# Input_switch.net
KiCad netlist of a schematic drawn in Altium Designer
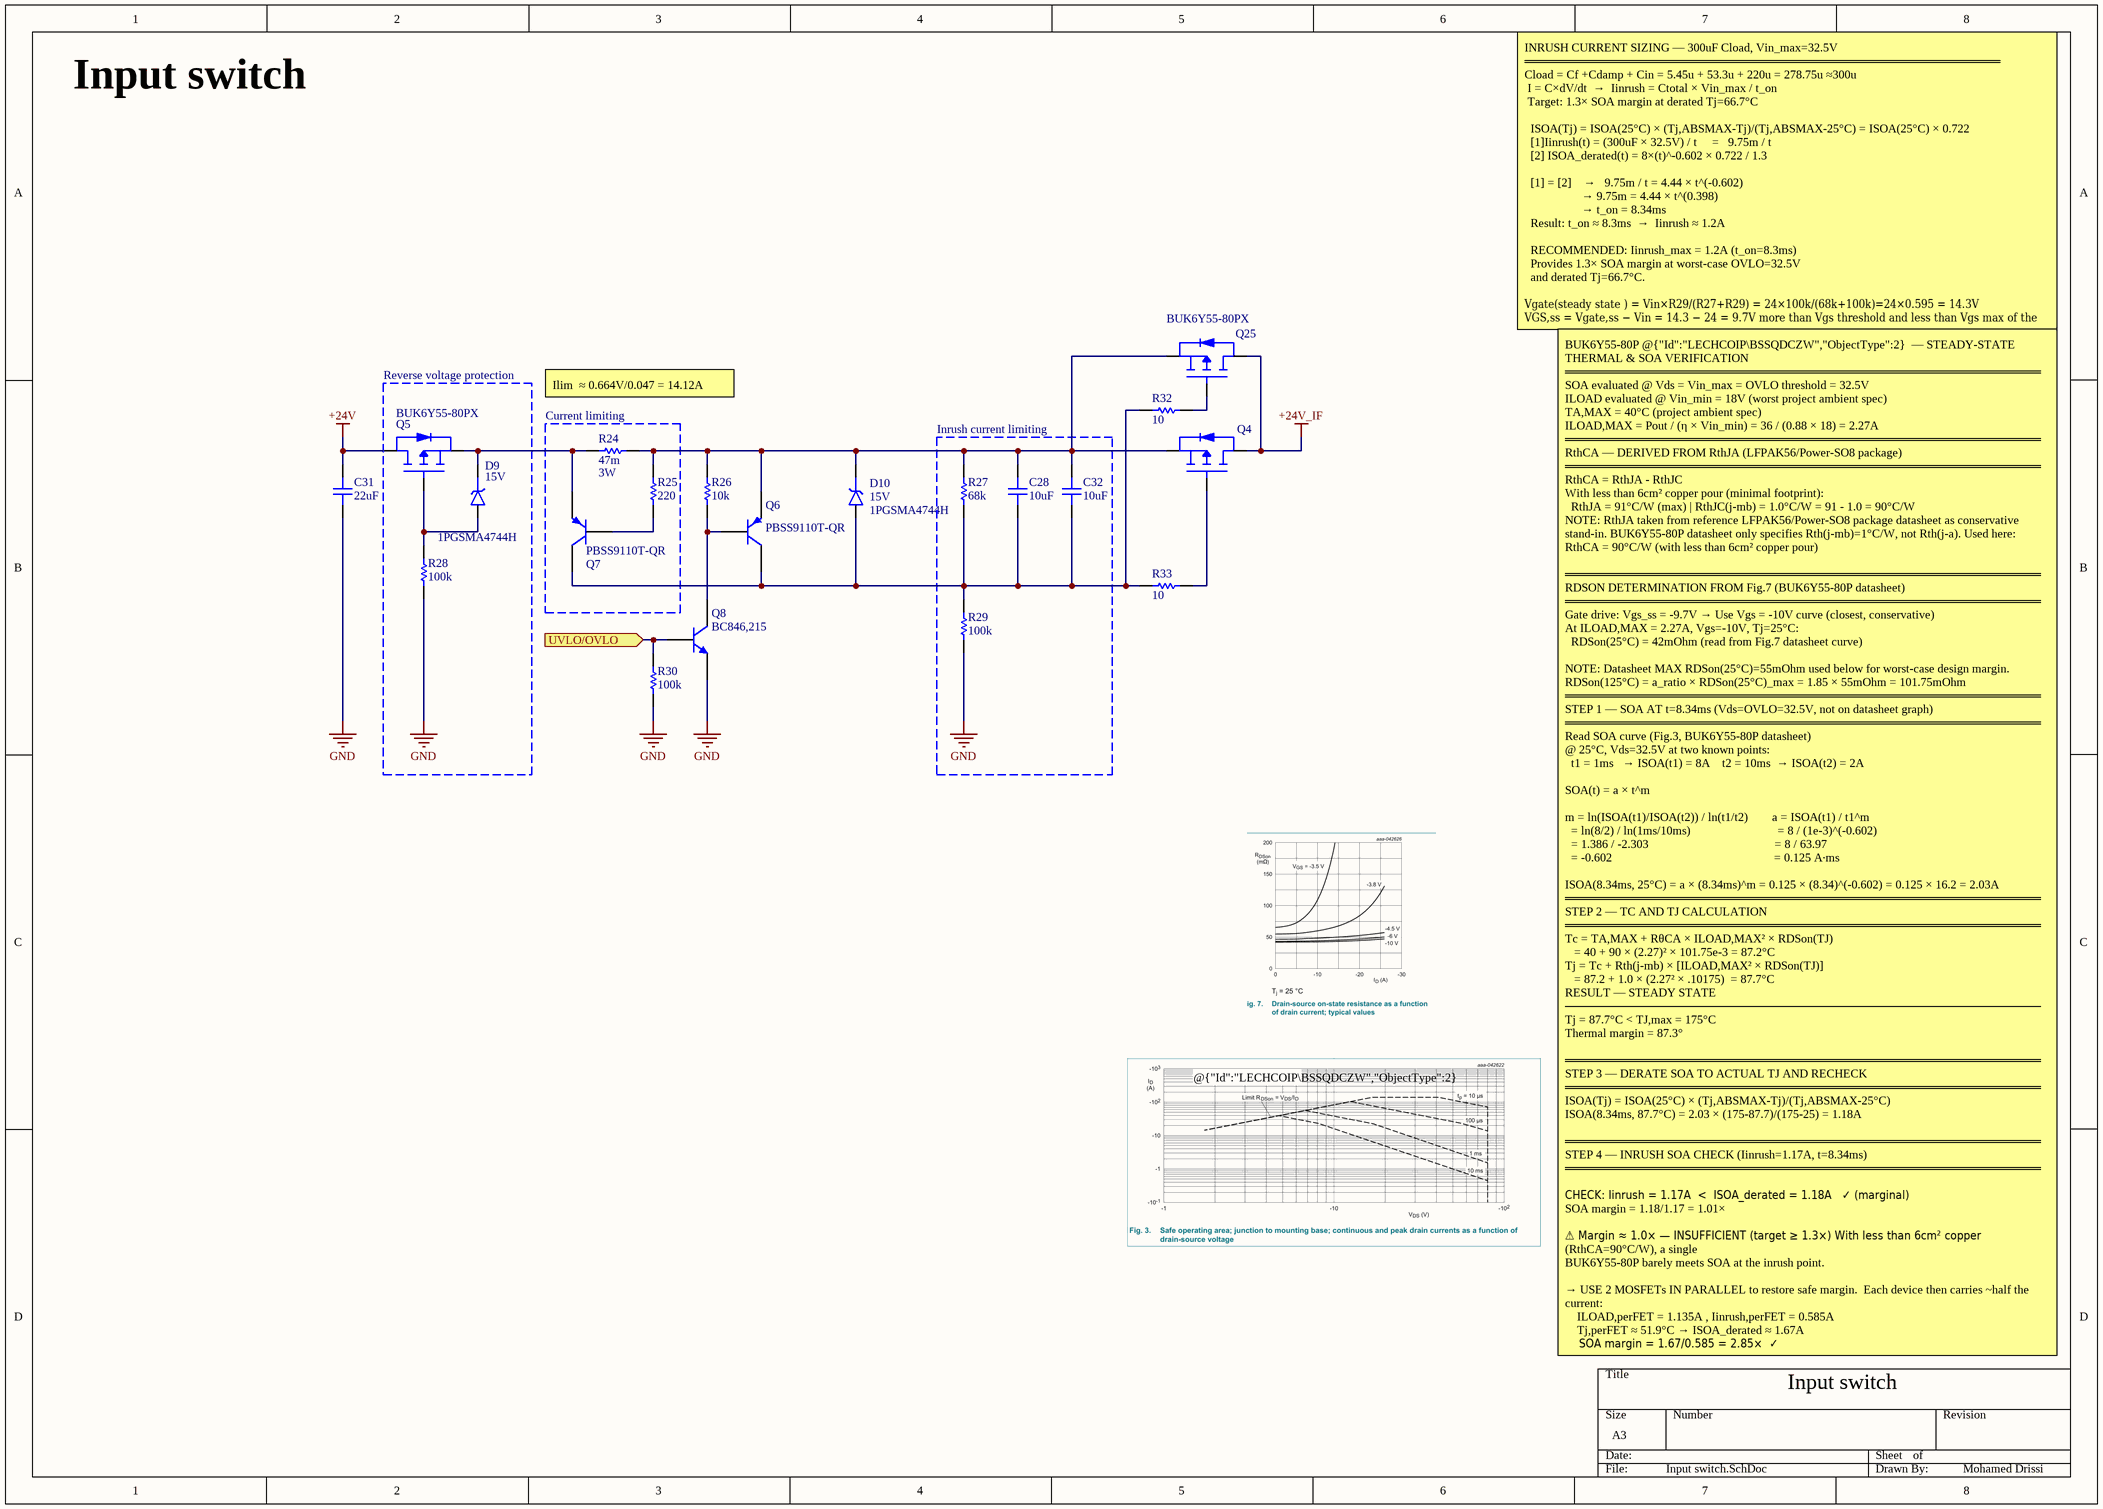
[diagram p0: Input switch.SchDoc]

(export (version "E")
  (design (tool "Eeschema 10.0.6"))
  (components
    (comp (ref "C28")
      (value "GRM32EC72A106KE05L")
      (footprint "cap_1210")
      (description "100V 10uF X7S ±10% 1210 Multilayer Ceramic Capacitors MLCC - SMD/SMT ROHS")
      (fields
        (field (name "MANUFACTURER") "Murata")
        (field (name "TOLERANCE") "10%")
        (field (name "CAPACITANCE") "10uF")
      )
      (libsource (lib "Inverting buck boost") (part "Murata GRM32EC72A106KE05L"))
    )
    (comp (ref "C31")
      (value "GMC43X7R226K50NT")
      (footprint "CAP_1812")
      (description "1812 Mlcc 22UF 50V 10% X7R")
      (fields (field (name "MANUFACTURER") "Cal-Chip Electronics") (field (name "CAPACITANCE") "22uF"))
      (libsource (lib "Inverting buck boost") (part "Cal-chip GMC43X7R226K50NT"))
    )
    (comp (ref "C32")
      (value "GRM32EC72A106KE05L")
      (footprint "cap_1210")
      (description "100V 10uF X7S ±10% 1210 Multilayer Ceramic Capacitors MLCC - SMD/SMT ROHS")
      (fields
        (field (name "MANUFACTURER") "Murata")
        (field (name "TOLERANCE") "10%")
        (field (name "CAPACITANCE") "10uF")
      )
      (libsource (lib "Inverting buck boost") (part "Murata GRM32EC72A106KE05L"))
    )
    (comp (ref "D9")
      (value "1PGSMA4744H")
      (footprint "DO-214AC")
      (description "Zener Diode, 15V V(Z), 5%, 1W, Silicon, Unidirectional, DO-214AC")
      (fields (field (name "MANUFACTURER") "Taiwan Semiconductor") (field (name "REFERENCE VOLTAGE") "15V"))
      (libsource (lib "Inverting buck boost") (part "Taiwan semiconductor 1PGSMA4744H"))
    )
    (comp (ref "D10")
      (value "1PGSMA4744H")
      (footprint "DO-214AC")
      (description "Zener Diode, 15V V(Z), 5%, 1W, Silicon, Unidirectional, DO-214AC")
      (fields (field (name "MANUFACTURER") "Taiwan Semiconductor") (field (name "REFERENCE VOLTAGE") "15V"))
      (libsource (lib "Inverting buck boost") (part "Taiwan semiconductor 1PGSMA4744H"))
    )
    (comp (ref "Q4")
      (value "BUK6Y55-80PX")
      (footprint "LFPAK56")
      (description "80 V, P-channel Trench MOSFET")
      (fields (field (name "MANUFACTURER") "Nexperia"))
      (libsource (lib "Inverting buck boost") (part "Nexp BUK6Y55-80PX"))
    )
    (comp (ref "Q5")
      (value "BUK6Y55-80PX")
      (footprint "LFPAK56")
      (description "80 V, P-channel Trench MOSFET")
      (fields (field (name "MANUFACTURER") "Nexperia"))
      (libsource (lib "Inverting buck boost") (part "Nexp BUK6Y55-80PX"))
    )
    (comp (ref "Q6")
      (value "PBSS9110T-QR")
      (footprint "SOT23")
      (description "Bipolar Transistors - BJT 100 V, 1 A PNP low VCEsat transistor")
      (fields (field (name "MANUFACTURER") "Nexperia"))
      (libsource (lib "Inverting buck boost") (part "NXP PBSS9110T-QR"))
    )
    (comp (ref "Q7")
      (value "PBSS9110T-QR")
      (footprint "SOT23")
      (description "Bipolar Transistors - BJT 100 V, 1 A PNP low VCEsat transistor")
      (fields (field (name "MANUFACTURER") "Nexperia"))
      (libsource (lib "Inverting buck boost") (part "NXP PBSS9110T-QR"))
    )
    (comp (ref "Q8")
      (value "BC846,215")
      (footprint "sot23")
      (description "BC846 Series 65 V 100 mA SMT NPN General Purpose Transistor - SOT-23")
      (fields (field (name "MANUFACTURER") "Nexperia"))
      (libsource (lib "Inverting buck boost") (part "NXP BC846,215"))
    )
    (comp (ref "Q25")
      (value "BUK6Y55-80PX")
      (footprint "LFPAK56")
      (description "80 V, P-channel Trench MOSFET")
      (fields (field (name "MANUFACTURER") "Nexperia"))
      (libsource (lib "Inverting buck boost") (part "Nexp BUK6Y55-80PX"))
    )
    (comp (ref "R24")
      (value "RLW73PA3FR047TE")
      (footprint "RES_1225")
      (description "Fixed Resistor, Metal Glaze/thick Film, 3W, 1% +/-Tol, 200ppm/Cel, 1225")
      (fields
        (field (name "MANUFACTURER") "TE Connectivity")
        (field (name "POWER RATING") "3W")
        (field (name "TOLERANCE") "1%")
        (field (name "RESISTANCE") "47m")
      )
      (libsource (lib "Inverting buck boost") (part "TE RLW73PA3FR047TE"))
    )
    (comp (ref "R25")
      (value "CRGCQ0603J220R")
      (footprint "res_0603")
      (description "Res Thick Film 0603 220 Ohm 5% 0.1W(1/10W) ±100ppm/C Pad SMD Automotive T/R")
      (fields
        (field (name "MANUFACTURER") "TE Connectivity")
        (field (name "TOLERANCE") "5%")
        (field (name "RESISTANCE") "220")
      )
      (libsource (lib "Inverting buck boost") (part "TE CRGCQ0603J220R"))
    )
    (comp (ref "R26")
      (value "RC0603FR-0710KL")
      (footprint "res_0603")
      (description "100mW Thick Film Resistors ±100ppm/℃ ±1% 10kΩ 0603 Chip Resistor - Surface Mount ROHS")
      (fields
        (field (name "MANUFACTURER") "Yageo Group")
        (field (name "TOLERANCE") "1%")
        (field (name "RESISTANCE") "10k")
      )
      (libsource (lib "Inverting buck boost") (part "YAGEO RC0603FR-0710KL"))
    )
    (comp (ref "R27")
      (value "CRGCQ0603J68K")
      (footprint "res_0603")
      (description "Res Thick Film 0603 68K Ohm 5% 0.1W(1/10W) ±100ppm/C Pad SMD Automotive T/R")
      (fields
        (field (name "MANUFACTURER") "TE Connectivity")
        (field (name "TOLERANCE") "5%")
        (field (name "RESISTANCE") "68k")
      )
      (libsource (lib "Inverting buck boost") (part "TE CRGCQ0603J68K"))
    )
    (comp (ref "R28")
      (value "CRCW0603100KFKEA")
      (footprint "res_0603")
      (description "Res Thick Film 0603 100K Ohm 1% 1/3W ±100ppm/°C Molded SMD SMD Paper T/R")
      (fields
        (field (name "MANUFACTURER") "Vishay")
        (field (name "MANUFACTURER PART NUMBER") "CRCW0603100KFKEAHP")
        (field (name "RESISTANCE") "100k")
      )
      (libsource (lib "Inverting buck boost") (part "Vishay CRCW0603100KFKEAHP"))
    )
    (comp (ref "R29")
      (value "CRCW0603100KFKEA")
      (footprint "res_0603")
      (description "Res Thick Film 0603 100K Ohm 1% 1/3W ±100ppm/°C Molded SMD SMD Paper T/R")
      (fields
        (field (name "MANUFACTURER") "Vishay")
        (field (name "MANUFACTURER PART NUMBER") "CRCW0603100KFKEAHP")
        (field (name "RESISTANCE") "100k")
      )
      (libsource (lib "Inverting buck boost") (part "Vishay CRCW0603100KFKEAHP"))
    )
    (comp (ref "R30")
      (value "CRCW0603100KFKEA")
      (footprint "res_0603")
      (description "Res Thick Film 0603 100K Ohm 1% 1/3W ±100ppm/°C Molded SMD SMD Paper T/R")
      (fields
        (field (name "MANUFACTURER") "Vishay")
        (field (name "MANUFACTURER PART NUMBER") "CRCW0603100KFKEAHP")
        (field (name "RESISTANCE") "100k")
      )
      (libsource (lib "Inverting buck boost") (part "Vishay CRCW0603100KFKEAHP"))
    )
    (comp (ref "R32")
      (value "RC0603FR-0710RL")
      (footprint "res_0603")
      (description "Res Thick Film 0603 10 Ohm 1% 0.1W(1/10W) ±200ppm/C Pad SMD T/R")
      (fields (field (name "RESISTANCE") "10"))
      (libsource (lib "Inverting buck boost") (part "Yageo RC0603FR-0710RL"))
    )
    (comp (ref "R33")
      (value "RC0603FR-0710RL")
      (footprint "res_0603")
      (description "Res Thick Film 0603 10 Ohm 1% 0.1W(1/10W) ±200ppm/C Pad SMD T/R")
      (fields (field (name "RESISTANCE") "10"))
      (libsource (lib "Inverting buck boost") (part "Yageo RC0603FR-0710RL"))
    )
  )
  (nets
    (net (code "1") (name "+24V") (class "Default")
      (node (ref "C31") (pin "2") (pinfunction "2_2") (pintype "passive"))
      (node (ref "Q5") (pin "MB") (pinfunction "D_MB") (pintype "passive"))
    )
    (net (code "2") (name "+24V_IF") (class "Default")
      (node (ref "Q25") (pin "MB") (pinfunction "D_MB") (pintype "passive"))
      (node (ref "Q4") (pin "MB") (pinfunction "D_MB") (pintype "passive"))
    )
    (net (code "3") (name "/UVLO{slash}OVLO") (class "Default")
      (node (ref "Q8") (pin "1") (pinfunction "B_1") (pintype "passive"))
      (node (ref "R30") (pin "2") (pinfunction "2_2") (pintype "passive"))
    )
    (net (code "4") (name "GND") (class "Default")
      (node (ref "C31") (pin "1") (pinfunction "1_1") (pintype "passive"))
      (node (ref "Q8") (pin "2") (pinfunction "E_2") (pintype "passive"))
      (node (ref "R28") (pin "1") (pinfunction "1_1") (pintype "passive"))
      (node (ref "R29") (pin "1") (pinfunction "1_1") (pintype "passive"))
      (node (ref "R30") (pin "1") (pinfunction "1_1") (pintype "passive"))
    )
    (net (code "5") (name "Net-(Q4-G)") (class "Default")
      (node (ref "Q4") (pin "4") (pinfunction "G_4") (pintype "passive"))
      (node (ref "R33") (pin "1") (pinfunction "1_1") (pintype "passive"))
    )
    (net (code "6") (name "Net-(Q5-G)") (class "Default")
      (node (ref "D9") (pin "A") (pinfunction "A_A") (pintype "passive"))
      (node (ref "Q5") (pin "4") (pinfunction "G_4") (pintype "passive"))
      (node (ref "R28") (pin "2") (pinfunction "2_2") (pintype "passive"))
    )
    (net (code "7") (name "Net-(Q5-S)") (class "Default")
      (node (ref "D9") (pin "C") (pinfunction "C_C") (pintype "passive"))
      (node (ref "Q5") (pin "1") (pinfunction "S_1") (pintype "passive"))
      (node (ref "Q7") (pin "2") (pinfunction "E_2") (pintype "passive"))
      (node (ref "R24") (pin "1") (pinfunction "1_1") (pintype "passive"))
    )
    (net (code "8") (name "Net-(Q6-B)") (class "Default")
      (node (ref "Q6") (pin "1") (pinfunction "B_1") (pintype "passive"))
      (node (ref "Q8") (pin "3") (pinfunction "C_3") (pintype "passive"))
      (node (ref "R26") (pin "1") (pinfunction "1_1") (pintype "passive"))
    )
    (net (code "9") (name "Net-(Q6-C)") (class "Default")
      (node (ref "C28") (pin "1") (pinfunction "1_1") (pintype "passive"))
      (node (ref "C32") (pin "1") (pinfunction "1_1") (pintype "passive"))
      (node (ref "D10") (pin "A") (pinfunction "A_A") (pintype "passive"))
      (node (ref "Q6") (pin "3") (pinfunction "C_3") (pintype "passive"))
      (node (ref "Q7") (pin "3") (pinfunction "C_3") (pintype "passive"))
      (node (ref "R27") (pin "1") (pinfunction "1_1") (pintype "passive"))
      (node (ref "R29") (pin "2") (pinfunction "2_2") (pintype "passive"))
      (node (ref "R32") (pin "2") (pinfunction "2_2") (pintype "passive"))
      (node (ref "R33") (pin "2") (pinfunction "2_2") (pintype "passive"))
    )
    (net (code "10") (name "Net-(Q7-B)") (class "Default")
      (node (ref "Q7") (pin "1") (pinfunction "B_1") (pintype "passive"))
      (node (ref "R25") (pin "1") (pinfunction "1_1") (pintype "passive"))
    )
    (net (code "11") (name "Net-(Q25-G)") (class "Default")
      (node (ref "Q25") (pin "4") (pinfunction "G_4") (pintype "passive"))
      (node (ref "R32") (pin "1") (pinfunction "1_1") (pintype "passive"))
    )
    (net (code "12") (name "Net-(Q25-S)") (class "Default")
      (node (ref "C28") (pin "2") (pinfunction "2_2") (pintype "passive"))
      (node (ref "C32") (pin "2") (pinfunction "2_2") (pintype "passive"))
      (node (ref "D10") (pin "C") (pinfunction "C_C") (pintype "passive"))
      (node (ref "Q25") (pin "1") (pinfunction "S_1") (pintype "passive"))
      (node (ref "Q4") (pin "1") (pinfunction "S_1") (pintype "passive"))
      (node (ref "Q6") (pin "2") (pinfunction "E_2") (pintype "passive"))
      (node (ref "R24") (pin "2") (pinfunction "2_2") (pintype "passive"))
      (node (ref "R25") (pin "2") (pinfunction "2_2") (pintype "passive"))
      (node (ref "R26") (pin "2") (pinfunction "2_2") (pintype "passive"))
      (node (ref "R27") (pin "2") (pinfunction "2_2") (pintype "passive"))
    )
  )
)
